# GameIT_Industrial.net
KiCad netlist of a schematic drawn in EAGLE
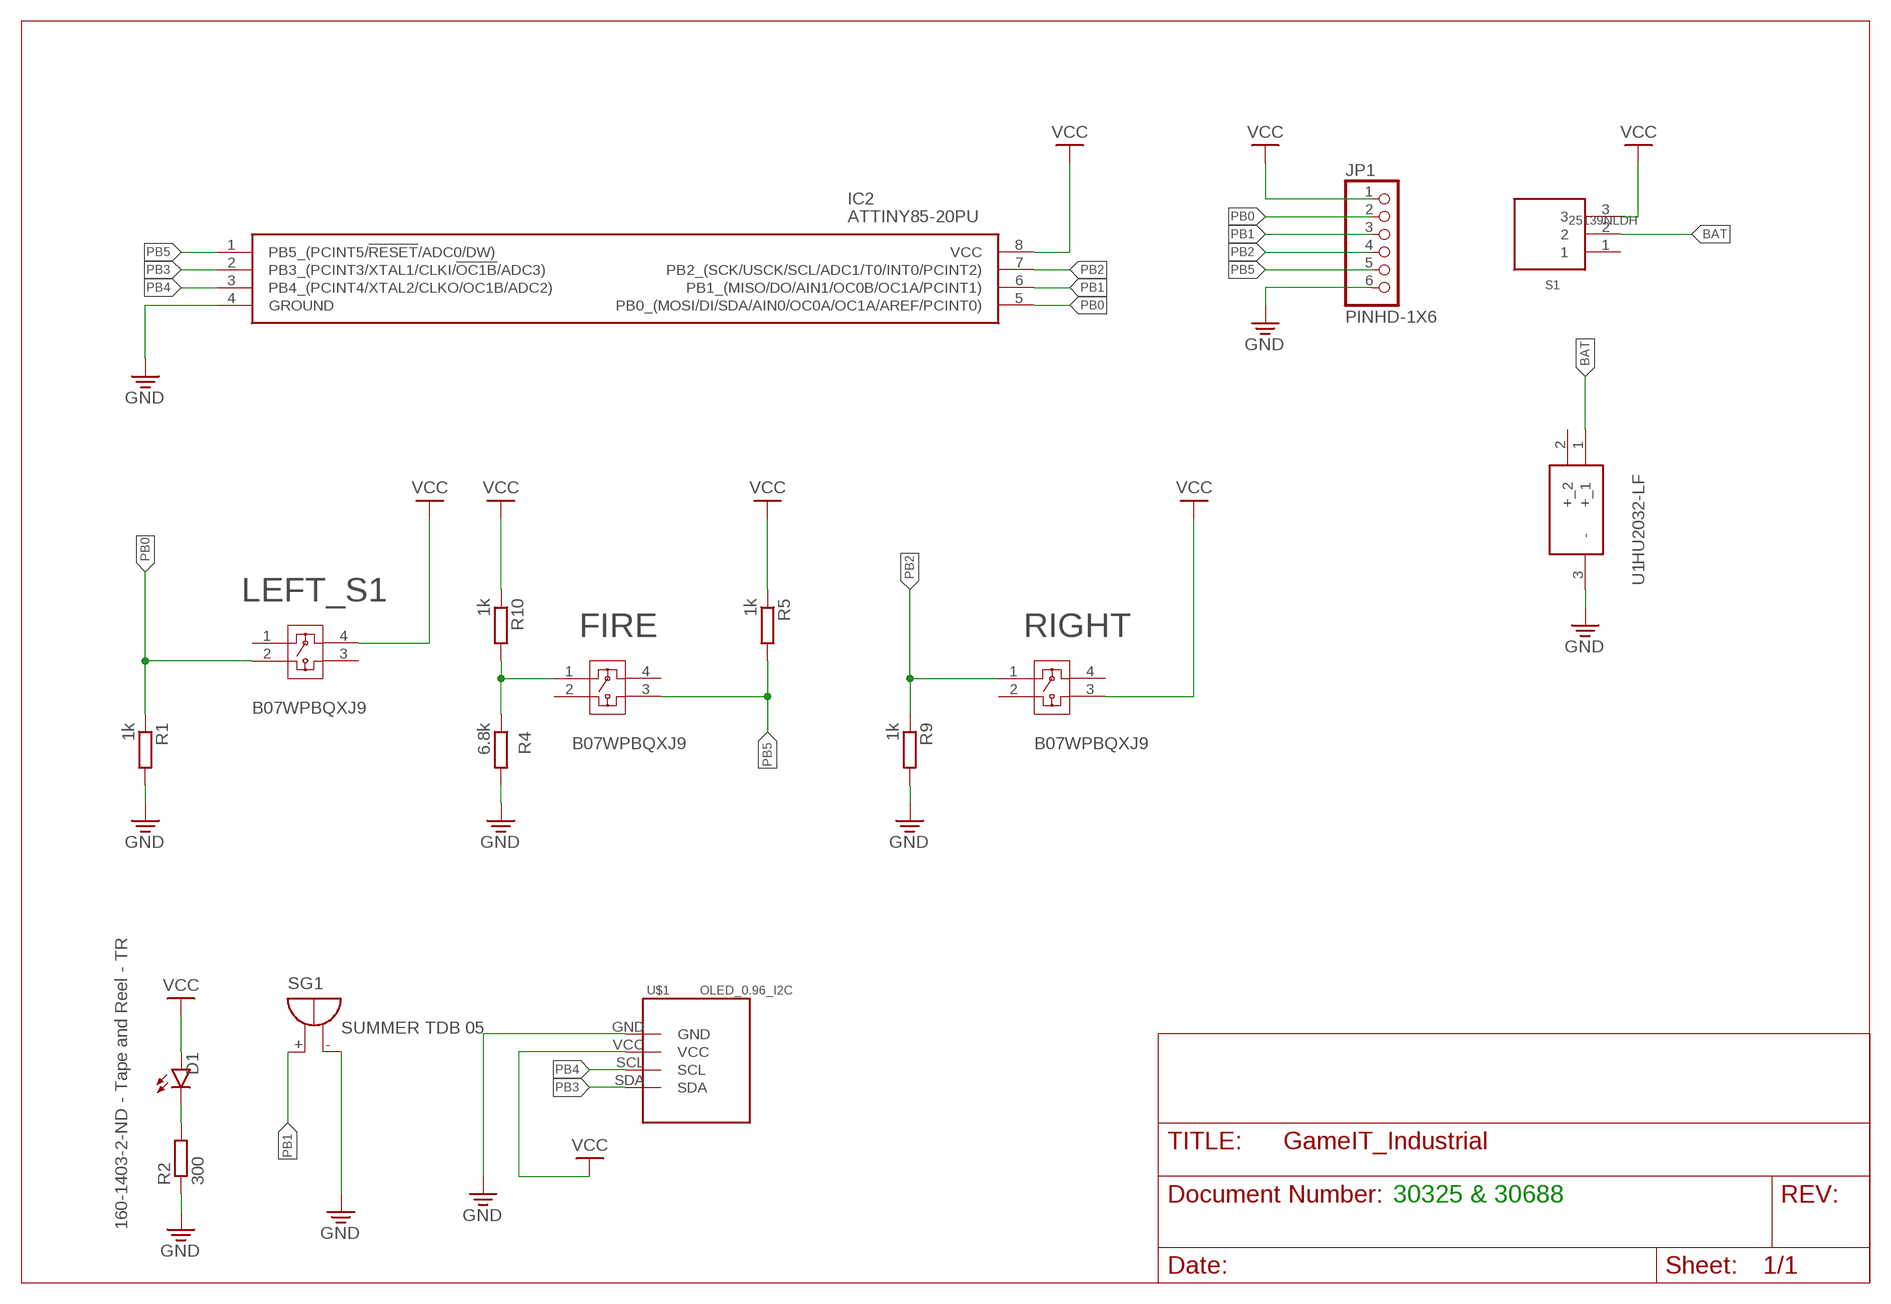
[diagram p0: schematic, sheet 1]

(export (version "E")
  (design (tool "Eeschema 10.0.6"))
  (components
    (comp (ref "D1")
      (value "LED_GREEN")
      (footprint "eagle-import:CHIPLED_1206")
      (libsource (lib "eagle-import") (part "LEDCHIPLED_1206"))
    )
    (comp (ref "FIRE")
      (value "COM-10302COM-10302_SPK")
      (footprint "eagle-import:COM-10302_SPK")
      (fields
        (field (name "MANUFACTURER_PART_NUMBER") "COM-10302")
        (field (name "COPYRIGHT") "Copyright (C) 2023 Ultra Librarian. All rights reserved.")
      )
      (libsource (lib "eagle-import") (part "COM-10302COM-10302_SPK"))
    )
    (comp (ref "IC2")
      (value "ATTINY85-20PU")
      (footprint "eagle-import:DIP781W56P254L950H533Q8N")
      (fields (field (name "MOUSER_PART_NUMBER") "556-ATTINY85-20PU"))
      (libsource (lib "eagle-import") (part "ATTINY85-20PU"))
    )
    (comp (ref "JP1")
      (value "PINHD-1X6")
      (footprint "eagle-import:1X06")
      (fields (field (name "MANUFACTURER") "Generic"))
      (libsource (lib "eagle-import") (part "PINHD-1X6"))
    )
    (comp (ref "LEFT_S1")
      (value "COM-10302COM-10302_SPK")
      (footprint "eagle-import:COM-10302_SPK")
      (fields
        (field (name "MANUFACTURER_PART_NUMBER") "COM-10302")
        (field (name "COPYRIGHT") "Copyright (C) 2023 Ultra Librarian. All rights reserved.")
      )
      (libsource (lib "eagle-import") (part "COM-10302COM-10302_SPK"))
    )
    (comp (ref "R1")
      (value "1k")
      (footprint "eagle-import:R1206")
      (libsource (lib "eagle-import") (part "R-EU_R1206"))
    )
    (comp (ref "R2")
      (value "300")
      (footprint "eagle-import:R1206")
      (libsource (lib "eagle-import") (part "R-EU_R1206"))
    )
    (comp (ref "R4")
      (value "6.8k")
      (footprint "eagle-import:R1206")
      (libsource (lib "eagle-import") (part "R-EU_R1206"))
    )
    (comp (ref "R5")
      (value "1k")
      (footprint "eagle-import:R1206")
      (libsource (lib "eagle-import") (part "R-EU_R1206"))
    )
    (comp (ref "R9")
      (value "1k")
      (footprint "eagle-import:R1206")
      (libsource (lib "eagle-import") (part "R-EU_R1206"))
    )
    (comp (ref "R10")
      (value "1k")
      (footprint "eagle-import:R1206")
      (libsource (lib "eagle-import") (part "R-EU_R1206"))
    )
    (comp (ref "RIGHT")
      (value "COM-10302COM-10302_SPK")
      (footprint "eagle-import:COM-10302_SPK")
      (fields
        (field (name "MANUFACTURER_PART_NUMBER") "COM-10302")
        (field (name "COPYRIGHT") "Copyright (C) 2023 Ultra Librarian. All rights reserved.")
      )
      (libsource (lib "eagle-import") (part "COM-10302COM-10302_SPK"))
    )
    (comp (ref "S1")
      (value "25139NLDH")
      (footprint "eagle-import:25139NLDH")
      (fields (field (name "MOUSER_PART_NUMBER") "642-25139NLDH"))
      (libsource (lib "eagle-import") (part "25139NLDH"))
    )
    (comp (ref "SG1")
      (value "F/HMB")
      (footprint "eagle-import:F_HMB")
      (libsource (lib "eagle-import") (part "F/HMB"))
    )
    (comp (ref "U$1")
      (value "OLED_0.96_I2C")
      (footprint "eagle-import:OLED_0.96_I2C")
      (libsource (lib "eagle-import") (part "OLED_0.96_I2C"))
    )
    (comp (ref "U1")
      (value "HU2032-LF")
      (footprint "eagle-import:HU2032LF")
      (fields (field (name "MOUSER_PART_NUMBER") "614-HU2032-LF"))
      (libsource (lib "eagle-import") (part "HU2032-LF"))
    )
  )
  (nets
    (net (code "1") (name "BAT") (class "Default")
      (node (ref "S1") (pin "2") (pinfunction "2_2") (pintype "bidirectional"))
      (node (ref "U1") (pin "1") (pinfunction "+_1_1") (pintype "bidirectional"))
    )
    (net (code "2") (name "GND") (class "Default")
      (node (ref "IC2") (pin "4") (pinfunction "GROUND_4") (pintype "power_in"))
      (node (ref "JP1") (pin "6") (pinfunction "6_6") (pintype "passive"))
      (node (ref "R1") (pin "2") (pinfunction "2_2") (pintype "passive"))
      (node (ref "R2") (pin "1") (pinfunction "1_1") (pintype "passive"))
      (node (ref "R4") (pin "2") (pinfunction "2_2") (pintype "passive"))
      (node (ref "R9") (pin "2") (pinfunction "2_2") (pintype "passive"))
      (node (ref "SG1") (pin "-") (pinfunction "-_-") (pintype "passive"))
      (node (ref "U$1") (pin "GND") (pinfunction "GND_GND") (pintype "bidirectional"))
      (node (ref "U1") (pin "3") (pinfunction "-_3") (pintype "bidirectional"))
    )
    (net (code "3") (name "Net-(D1-PadC)") (class "Default")
      (node (ref "D1") (pin "C") (pinfunction "C_C") (pintype "passive"))
      (node (ref "R2") (pin "2") (pinfunction "2_2") (pintype "passive"))
    )
    (net (code "4") (name "Net-(FIRE-Pad1)") (class "Default")
      (node (ref "FIRE") (pin "1") (pinfunction "1_1") (pintype "passive"))
      (node (ref "R10") (pin "2") (pinfunction "2_2") (pintype "passive"))
      (node (ref "R4") (pin "1") (pinfunction "1_1") (pintype "passive"))
    )
    (net (code "5") (name "PB0") (class "Default")
      (node (ref "IC2") (pin "5") (pinfunction "PB0_(MOSI/DI/SDA/AIN0/OC0A/OC1A/AREF/PCINT0)_5") (pintype "bidirectional"))
      (node (ref "JP1") (pin "2") (pinfunction "2_2") (pintype "passive"))
      (node (ref "LEFT_S1") (pin "2") (pinfunction "2_2") (pintype "passive"))
      (node (ref "R1") (pin "1") (pinfunction "1_1") (pintype "passive"))
    )
    (net (code "6") (name "PB1") (class "Default")
      (node (ref "IC2") (pin "6") (pinfunction "PB1_(MISO/DO/AIN1/OC0B/OC1A/PCINT1)_6") (pintype "bidirectional"))
      (node (ref "JP1") (pin "3") (pinfunction "3_3") (pintype "passive"))
      (node (ref "SG1") (pin "+") (pinfunction "+_+") (pintype "passive"))
    )
    (net (code "7") (name "PB2") (class "Default")
      (node (ref "IC2") (pin "7") (pinfunction "PB2_(SCK/USCK/SCL/ADC1/T0/INT0/PCINT2)_7") (pintype "bidirectional"))
      (node (ref "JP1") (pin "4") (pinfunction "4_4") (pintype "passive"))
      (node (ref "R9") (pin "1") (pinfunction "1_1") (pintype "passive"))
      (node (ref "RIGHT") (pin "1") (pinfunction "1_1") (pintype "passive"))
    )
    (net (code "8") (name "PB3") (class "Default")
      (node (ref "IC2") (pin "2") (pinfunction "PB3_(PCINT3/XTAL1/CLKI/~{OC1B}/ADC3)_2") (pintype "bidirectional"))
      (node (ref "U$1") (pin "SDA") (pinfunction "SDA_SDA") (pintype "bidirectional"))
    )
    (net (code "9") (name "PB4") (class "Default")
      (node (ref "IC2") (pin "3") (pinfunction "PB4_(PCINT4/XTAL2/CLKO/OC1B/ADC2)_3") (pintype "bidirectional"))
      (node (ref "U$1") (pin "SCL") (pinfunction "SCL_SCL") (pintype "bidirectional"))
    )
    (net (code "10") (name "PB5") (class "Default")
      (node (ref "FIRE") (pin "3") (pinfunction "3_3") (pintype "passive"))
      (node (ref "IC2") (pin "1") (pinfunction "PB5_(PCINT5/~{RESET}/ADC0/DW)_1") (pintype "bidirectional"))
      (node (ref "JP1") (pin "5") (pinfunction "5_5") (pintype "passive"))
      (node (ref "R5") (pin "2") (pinfunction "2_2") (pintype "passive"))
    )
    (net (code "11") (name "VCC") (class "Default")
      (node (ref "D1") (pin "A") (pinfunction "A_A") (pintype "passive"))
      (node (ref "IC2") (pin "8") (pinfunction "VCC_8") (pintype "power_in"))
      (node (ref "JP1") (pin "1") (pinfunction "1_1") (pintype "passive"))
      (node (ref "LEFT_S1") (pin "4") (pinfunction "4_4") (pintype "passive"))
      (node (ref "R10") (pin "1") (pinfunction "1_1") (pintype "passive"))
      (node (ref "R5") (pin "1") (pinfunction "1_1") (pintype "passive"))
      (node (ref "RIGHT") (pin "3") (pinfunction "3_3") (pintype "passive"))
      (node (ref "S1") (pin "3") (pinfunction "3_3") (pintype "bidirectional"))
      (node (ref "U$1") (pin "VCC") (pinfunction "VCC_VCC") (pintype "bidirectional"))
    )
    (net (code "12") (name "unconnected-(FIRE-Pad2)") (class "Default")
      (node (ref "FIRE") (pin "2") (pinfunction "2_2") (pintype "passive"))
    )
    (net (code "13") (name "unconnected-(FIRE-Pad4)") (class "Default")
      (node (ref "FIRE") (pin "4") (pinfunction "4_4") (pintype "passive"))
    )
    (net (code "14") (name "unconnected-(LEFT_S1-Pad1)") (class "Default")
      (node (ref "LEFT_S1") (pin "1") (pinfunction "1_1") (pintype "passive"))
    )
    (net (code "15") (name "unconnected-(LEFT_S1-Pad3)") (class "Default")
      (node (ref "LEFT_S1") (pin "3") (pinfunction "3_3") (pintype "passive"))
    )
    (net (code "16") (name "unconnected-(RIGHT-Pad2)") (class "Default")
      (node (ref "RIGHT") (pin "2") (pinfunction "2_2") (pintype "passive"))
    )
    (net (code "17") (name "unconnected-(RIGHT-Pad4)") (class "Default")
      (node (ref "RIGHT") (pin "4") (pinfunction "4_4") (pintype "passive"))
    )
    (net (code "18") (name "unconnected-(S1-Pad1)") (class "Default")
      (node (ref "S1") (pin "1") (pinfunction "1_1") (pintype "bidirectional"))
    )
    (net (code "19") (name "unconnected-(U1-+_2-Pad2)") (class "Default")
      (node (ref "U1") (pin "2") (pinfunction "+_2_2") (pintype "bidirectional"))
    )
  )
)
